# xcodec_CS42526_A.net
KiCad netlist of a schematic drawn in EAGLE
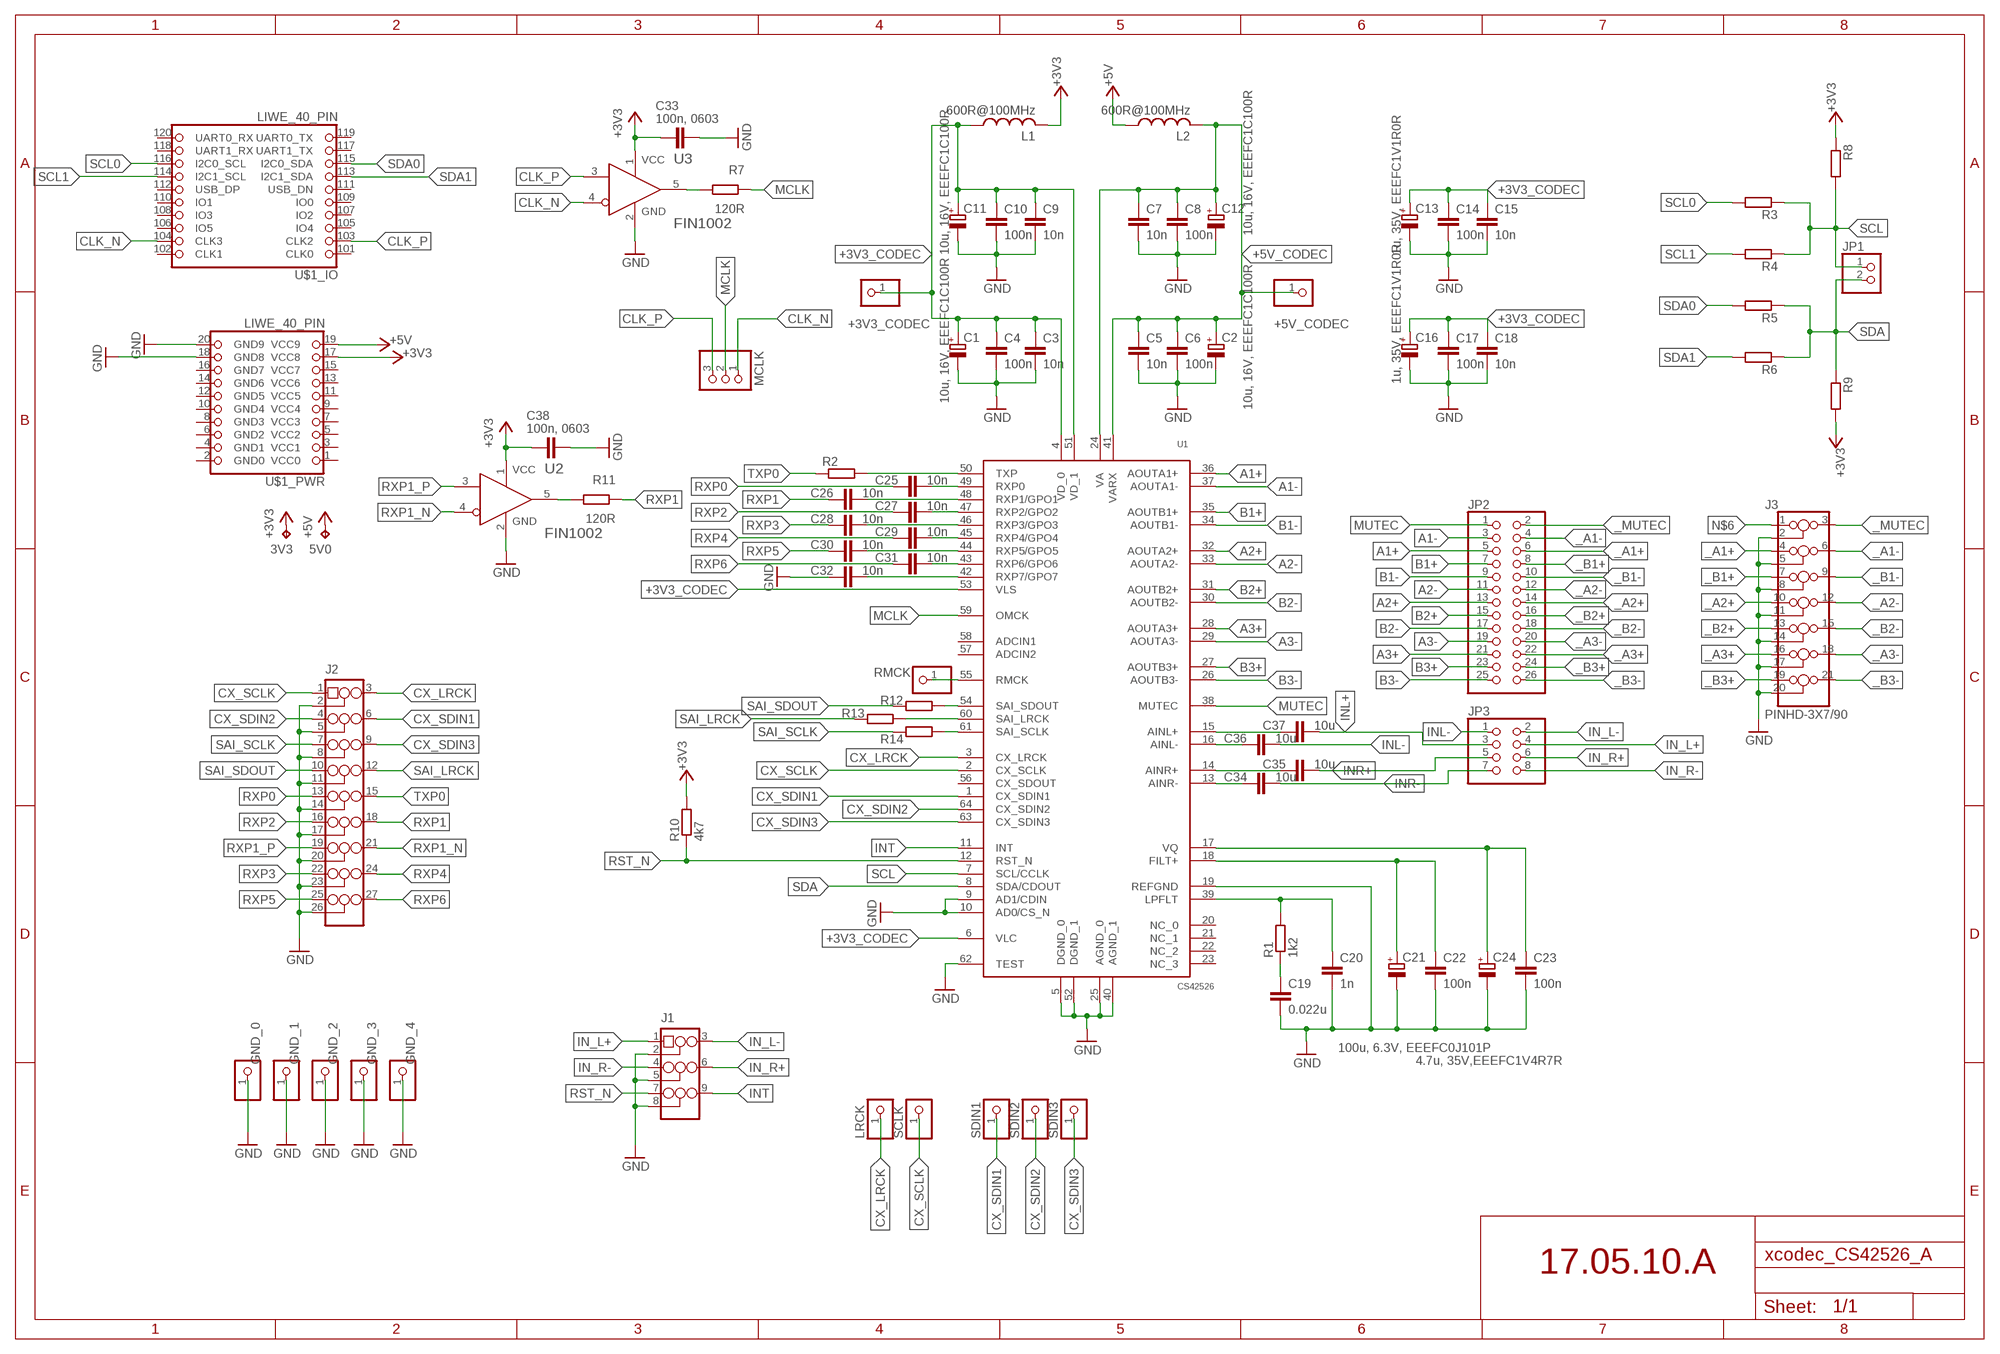
[diagram p0: schematic, sheet 1]

(export (version "E")
  (design (tool "Eeschema 10.0.6"))
  (components
    (comp (ref "+3V3_CODEC")
      (value "PINHD-1X1")
      (footprint "eagle-import:1X01")
      (libsource (lib "eagle-import") (part "PINHD-1X1"))
    )
    (comp (ref "+5V_CODEC")
      (value "PINHD-1X1")
      (footprint "eagle-import:1X01")
      (libsource (lib "eagle-import") (part "PINHD-1X1"))
    )
    (comp (ref "3V3")
      (value "TPTP14R")
      (footprint "eagle-import:TP14R")
      (libsource (lib "eagle-import") (part "TPTP14R"))
    )
    (comp (ref "5V0")
      (value "TPTP14R")
      (footprint "eagle-import:TP14R")
      (libsource (lib "eagle-import") (part "TPTP14R"))
    )
    (comp (ref "C1")
      (value "10u, 16V, EEEFC1C100R")
      (footprint "eagle-import:EEE-FC1V1R0AR")
      (libsource (lib "eagle-import") (part "C-POL_B"))
    )
    (comp (ref "C2")
      (value "10u, 16V, EEEFC1C100R")
      (footprint "eagle-import:EEE-FC1V1R0AR")
      (libsource (lib "eagle-import") (part "C-POL_B"))
    )
    (comp (ref "C3")
      (value "10n")
      (footprint "eagle-import:C0603K")
      (libsource (lib "eagle-import") (part "C-EUC0603K"))
    )
    (comp (ref "C4")
      (value "100n")
      (footprint "eagle-import:C0603K")
      (libsource (lib "eagle-import") (part "C-EUC0603K"))
    )
    (comp (ref "C5")
      (value "10n")
      (footprint "eagle-import:C0603K")
      (libsource (lib "eagle-import") (part "C-EUC0603K"))
    )
    (comp (ref "C6")
      (value "100n")
      (footprint "eagle-import:C0603K")
      (libsource (lib "eagle-import") (part "C-EUC0603K"))
    )
    (comp (ref "C7")
      (value "10n")
      (footprint "eagle-import:C0603K")
      (libsource (lib "eagle-import") (part "C-EUC0603K"))
    )
    (comp (ref "C8")
      (value "100n")
      (footprint "eagle-import:C0603K")
      (libsource (lib "eagle-import") (part "C-EUC0603K"))
    )
    (comp (ref "C9")
      (value "10n")
      (footprint "eagle-import:C0603K")
      (libsource (lib "eagle-import") (part "C-EUC0603K"))
    )
    (comp (ref "C10")
      (value "100n")
      (footprint "eagle-import:C0603K")
      (libsource (lib "eagle-import") (part "C-EUC0603K"))
    )
    (comp (ref "C11")
      (value "10u, 16V, EEEFC1C100R")
      (footprint "eagle-import:EEE-FC1V1R0AR")
      (libsource (lib "eagle-import") (part "C-POL_B"))
    )
    (comp (ref "C12")
      (value "10u, 16V, EEEFC1C100R")
      (footprint "eagle-import:EEE-FC1V1R0AR")
      (libsource (lib "eagle-import") (part "C-POL_B"))
    )
    (comp (ref "C13")
      (value "1u, 35V, EEEFC1V1R0R")
      (footprint "eagle-import:EEE-FC1V1R0AR")
      (libsource (lib "eagle-import") (part "C-POL_B"))
    )
    (comp (ref "C14")
      (value "100n")
      (footprint "eagle-import:C0603K")
      (libsource (lib "eagle-import") (part "C-EUC0603K"))
    )
    (comp (ref "C15")
      (value "10n")
      (footprint "eagle-import:C0603K")
      (libsource (lib "eagle-import") (part "C-EUC0603K"))
    )
    (comp (ref "C16")
      (value "1u, 35V, EEEFC1V1R0R")
      (footprint "eagle-import:EEE-FC1V1R0AR")
      (libsource (lib "eagle-import") (part "C-POL_B"))
    )
    (comp (ref "C17")
      (value "100n")
      (footprint "eagle-import:C0603K")
      (libsource (lib "eagle-import") (part "C-EUC0603K"))
    )
    (comp (ref "C18")
      (value "10n")
      (footprint "eagle-import:C0603K")
      (libsource (lib "eagle-import") (part "C-EUC0603K"))
    )
    (comp (ref "C19")
      (value "0.022u")
      (footprint "eagle-import:C0603K")
      (libsource (lib "eagle-import") (part "C-EUC0603K"))
    )
    (comp (ref "C20")
      (value "1n")
      (footprint "eagle-import:C0603K")
      (libsource (lib "eagle-import") (part "C-EUC0603K"))
    )
    (comp (ref "C21")
      (value "100u, 6.3V, EEEFC0J101P")
      (footprint "eagle-import:EEE-FC1V220P")
      (libsource (lib "eagle-import") (part "C-POL_D"))
    )
    (comp (ref "C22")
      (value "100n")
      (footprint "eagle-import:C0603K")
      (libsource (lib "eagle-import") (part "C-EUC0603K"))
    )
    (comp (ref "C23")
      (value "100n")
      (footprint "eagle-import:C0603K")
      (libsource (lib "eagle-import") (part "C-EUC0603K"))
    )
    (comp (ref "C24")
      (value "4.7u, 35V,EEEFC1V4R7R")
      (footprint "eagle-import:EEE-FC1V1R0AR")
      (libsource (lib "eagle-import") (part "C-POL_B"))
    )
    (comp (ref "C25")
      (value "10n")
      (footprint "eagle-import:C0603K")
      (libsource (lib "eagle-import") (part "C-EUC0603K"))
    )
    (comp (ref "C26")
      (value "10n")
      (footprint "eagle-import:C0603K")
      (libsource (lib "eagle-import") (part "C-EUC0603K"))
    )
    (comp (ref "C27")
      (value "10n")
      (footprint "eagle-import:C0603K")
      (libsource (lib "eagle-import") (part "C-EUC0603K"))
    )
    (comp (ref "C28")
      (value "10n")
      (footprint "eagle-import:C0603K")
      (libsource (lib "eagle-import") (part "C-EUC0603K"))
    )
    (comp (ref "C29")
      (value "10n")
      (footprint "eagle-import:C0603K")
      (libsource (lib "eagle-import") (part "C-EUC0603K"))
    )
    (comp (ref "C30")
      (value "10n")
      (footprint "eagle-import:C0603K")
      (libsource (lib "eagle-import") (part "C-EUC0603K"))
    )
    (comp (ref "C31")
      (value "10n")
      (footprint "eagle-import:C0603K")
      (libsource (lib "eagle-import") (part "C-EUC0603K"))
    )
    (comp (ref "C32")
      (value "10n")
      (footprint "eagle-import:C0603K")
      (libsource (lib "eagle-import") (part "C-EUC0603K"))
    )
    (comp (ref "C33")
      (value "100n, 0603")
      (footprint "eagle-import:C0603K")
      (libsource (lib "eagle-import") (part "C-EUC0603K"))
    )
    (comp (ref "C34")
      (value "10u")
      (footprint "eagle-import:C0603K")
      (libsource (lib "eagle-import") (part "C-EUC0603K"))
    )
    (comp (ref "C35")
      (value "10u")
      (footprint "eagle-import:C0603K")
      (libsource (lib "eagle-import") (part "C-EUC0603K"))
    )
    (comp (ref "C36")
      (value "10u")
      (footprint "eagle-import:C0603K")
      (libsource (lib "eagle-import") (part "C-EUC0603K"))
    )
    (comp (ref "C37")
      (value "10u")
      (footprint "eagle-import:C0603K")
      (libsource (lib "eagle-import") (part "C-EUC0603K"))
    )
    (comp (ref "C38")
      (value "100n, 0603")
      (footprint "eagle-import:C0603K")
      (libsource (lib "eagle-import") (part "C-EUC0603K"))
    )
    (comp (ref "GND_0")
      (value "PINHD-1X1")
      (footprint "eagle-import:1X01")
      (libsource (lib "eagle-import") (part "PINHD-1X1"))
    )
    (comp (ref "GND_1")
      (value "PINHD-1X1")
      (footprint "eagle-import:1X01")
      (libsource (lib "eagle-import") (part "PINHD-1X1"))
    )
    (comp (ref "GND_2")
      (value "PINHD-1X1")
      (footprint "eagle-import:1X01")
      (libsource (lib "eagle-import") (part "PINHD-1X1"))
    )
    (comp (ref "GND_3")
      (value "PINHD-1X1")
      (footprint "eagle-import:1X01")
      (libsource (lib "eagle-import") (part "PINHD-1X1"))
    )
    (comp (ref "GND_4")
      (value "PINHD-1X1")
      (footprint "eagle-import:1X01")
      (libsource (lib "eagle-import") (part "PINHD-1X1"))
    )
    (comp (ref "J1")
      (value "PINHD-3X3/90")
      (footprint "eagle-import:3X03_90")
      (libsource (lib "eagle-import") (part "PINHD-3X3/90"))
    )
    (comp (ref "J2")
      (value "PINHD-3X9/90")
      (footprint "eagle-import:3X9_90")
      (libsource (lib "eagle-import") (part "PINHD-3X9/90"))
    )
    (comp (ref "J3")
      (value "PINHD-3X7/90")
      (footprint "eagle-import:3X07_90")
      (libsource (lib "eagle-import") (part "PINHD-3X7/90"))
    )
    (comp (ref "JP1")
      (value "PINHD-1X2")
      (footprint "eagle-import:1X02")
      (libsource (lib "eagle-import") (part "PINHD-1X2"))
    )
    (comp (ref "JP2")
      (value "PINHD-2X13")
      (footprint "eagle-import:2X13")
      (libsource (lib "eagle-import") (part "PINHD-2X13"))
    )
    (comp (ref "JP3")
      (value "PINHD-2X4")
      (footprint "eagle-import:2X04")
      (libsource (lib "eagle-import") (part "PINHD-2X4"))
    )
    (comp (ref "L1")
      (value "600R@100MHz")
      (footprint "eagle-import:L0603")
      (libsource (lib "eagle-import") (part "L0603(1608)"))
    )
    (comp (ref "L2")
      (value "600R@100MHz")
      (footprint "eagle-import:L0603")
      (libsource (lib "eagle-import") (part "L0603(1608)"))
    )
    (comp (ref "LRCK")
      (value "PINHD-1X1")
      (footprint "eagle-import:1X01")
      (libsource (lib "eagle-import") (part "PINHD-1X1"))
    )
    (comp (ref "MCLK")
      (value "PINHD-1X3")
      (footprint "eagle-import:1X03")
      (libsource (lib "eagle-import") (part "PINHD-1X3"))
    )
    (comp (ref "R1")
      (value "1k2")
      (footprint "eagle-import:R0603")
      (libsource (lib "eagle-import") (part "R-EU_R0603"))
    )
    (comp (ref "R2")
      (value "R-EU_R0603")
      (footprint "eagle-import:R0603")
      (libsource (lib "eagle-import") (part "R-EU_R0603"))
    )
    (comp (ref "R3")
      (value "R-EU_R0603")
      (footprint "eagle-import:R0603")
      (libsource (lib "eagle-import") (part "R-EU_R0603"))
    )
    (comp (ref "R4")
      (value "R-EU_R0603")
      (footprint "eagle-import:R0603")
      (libsource (lib "eagle-import") (part "R-EU_R0603"))
    )
    (comp (ref "R5")
      (value "R-EU_R0603")
      (footprint "eagle-import:R0603")
      (libsource (lib "eagle-import") (part "R-EU_R0603"))
    )
    (comp (ref "R6")
      (value "R-EU_R0603")
      (footprint "eagle-import:R0603")
      (libsource (lib "eagle-import") (part "R-EU_R0603"))
    )
    (comp (ref "R7")
      (value "120R")
      (footprint "eagle-import:R0603")
      (libsource (lib "eagle-import") (part "R-EU_R0603"))
    )
    (comp (ref "R8")
      (value "R-EU_R0603")
      (footprint "eagle-import:R0603")
      (libsource (lib "eagle-import") (part "R-EU_R0603"))
    )
    (comp (ref "R9")
      (value "R-EU_R0603")
      (footprint "eagle-import:R0603")
      (libsource (lib "eagle-import") (part "R-EU_R0603"))
    )
    (comp (ref "R10")
      (value "4k7")
      (footprint "eagle-import:R0603")
      (libsource (lib "eagle-import") (part "R-EU_R0603"))
    )
    (comp (ref "R11")
      (value "120R")
      (footprint "eagle-import:R0603")
      (libsource (lib "eagle-import") (part "R-EU_R0603"))
    )
    (comp (ref "R12")
      (value "R-EU_R0603")
      (footprint "eagle-import:R0603")
      (libsource (lib "eagle-import") (part "R-EU_R0603"))
    )
    (comp (ref "R13")
      (value "R-EU_R0603")
      (footprint "eagle-import:R0603")
      (libsource (lib "eagle-import") (part "R-EU_R0603"))
    )
    (comp (ref "R14")
      (value "R-EU_R0603")
      (footprint "eagle-import:R0603")
      (libsource (lib "eagle-import") (part "R-EU_R0603"))
    )
    (comp (ref "RMCK")
      (value "PINHD-1X1")
      (footprint "eagle-import:1X01")
      (libsource (lib "eagle-import") (part "PINHD-1X1"))
    )
    (comp (ref "SCLK")
      (value "PINHD-1X1")
      (footprint "eagle-import:1X01")
      (libsource (lib "eagle-import") (part "PINHD-1X1"))
    )
    (comp (ref "SDIN1")
      (value "PINHD-1X1")
      (footprint "eagle-import:1X01")
      (libsource (lib "eagle-import") (part "PINHD-1X1"))
    )
    (comp (ref "SDIN2")
      (value "PINHD-1X1")
      (footprint "eagle-import:1X01")
      (libsource (lib "eagle-import") (part "PINHD-1X1"))
    )
    (comp (ref "SDIN3")
      (value "PINHD-1X1")
      (footprint "eagle-import:1X01")
      (libsource (lib "eagle-import") (part "PINHD-1X1"))
    )
    (comp (ref "U$1")
      (value "LIWE_40_PIN")
      (footprint "eagle-import:LIWE_40_PIN_8X8")
      (libsource (lib "eagle-import") (part "LIWE_40_PIN"))
    )
    (comp (ref "U1")
      (value "CS42526")
      (footprint "eagle-import:LQFP_64")
      (libsource (lib "eagle-import") (part "CS42526"))
    )
    (comp (ref "U2")
      (value "FIN1002")
      (footprint "eagle-import:SOT95P280X140-5N")
      (libsource (lib "eagle-import") (part "FIN1002"))
    )
    (comp (ref "U3")
      (value "FIN1002")
      (footprint "eagle-import:SOT95P280X140-5N")
      (libsource (lib "eagle-import") (part "FIN1002"))
    )
  )
  (nets
    (net (code "1") (name "+3V3") (class "Default")
      (node (ref "3V3") (pin "TP") (pinfunction "TP_TP") (pintype "input"))
      (node (ref "C33") (pin "2") (pinfunction "2_2") (pintype "passive"))
      (node (ref "C38") (pin "2") (pinfunction "2_2") (pintype "passive"))
      (node (ref "L1") (pin "2") (pinfunction "2_2") (pintype "passive"))
      (node (ref "R10") (pin "2") (pinfunction "2_2") (pintype "passive"))
      (node (ref "R8") (pin "1") (pinfunction "1_1") (pintype "passive"))
      (node (ref "R9") (pin "2") (pinfunction "2_2") (pintype "passive"))
      (node (ref "U$1") (pin "17") (pinfunction "VCC8_17") (pintype "passive"))
      (node (ref "U2") (pin "1") (pinfunction "VCC_1") (pintype "power_in"))
      (node (ref "U3") (pin "1") (pinfunction "VCC_1") (pintype "power_in"))
    )
    (net (code "2") (name "+3V3_CODEC") (class "Default")
      (node (ref "+3V3_CODEC") (pin "1") (pinfunction "1_1") (pintype "passive"))
      (node (ref "C1") (pin "1") (pinfunction "+_1") (pintype "passive"))
      (node (ref "C10") (pin "1") (pinfunction "1_1") (pintype "passive"))
      (node (ref "C11") (pin "1") (pinfunction "+_1") (pintype "passive"))
      (node (ref "C13") (pin "1") (pinfunction "+_1") (pintype "passive"))
      (node (ref "C14") (pin "1") (pinfunction "1_1") (pintype "passive"))
      (node (ref "C15") (pin "1") (pinfunction "1_1") (pintype "passive"))
      (node (ref "C16") (pin "1") (pinfunction "+_1") (pintype "passive"))
      (node (ref "C17") (pin "1") (pinfunction "1_1") (pintype "passive"))
      (node (ref "C18") (pin "1") (pinfunction "1_1") (pintype "passive"))
      (node (ref "C3") (pin "1") (pinfunction "1_1") (pintype "passive"))
      (node (ref "C4") (pin "1") (pinfunction "1_1") (pintype "passive"))
      (node (ref "C9") (pin "1") (pinfunction "1_1") (pintype "passive"))
      (node (ref "L1") (pin "1") (pinfunction "1_1") (pintype "passive"))
      (node (ref "U1") (pin "4") (pinfunction "VD_0_4") (pintype "bidirectional"))
      (node (ref "U1") (pin "51") (pinfunction "VD_1_51") (pintype "bidirectional"))
      (node (ref "U1") (pin "53") (pinfunction "VLS_53") (pintype "bidirectional"))
      (node (ref "U1") (pin "6") (pinfunction "VLC_6") (pintype "bidirectional"))
    )
    (net (code "3") (name "+5V") (class "Default")
      (node (ref "5V0") (pin "TP") (pinfunction "TP_TP") (pintype "input"))
      (node (ref "L2") (pin "1") (pinfunction "1_1") (pintype "passive"))
      (node (ref "U$1") (pin "19") (pinfunction "VCC9_19") (pintype "passive"))
    )
    (net (code "4") (name "+5V_CODEC") (class "Default")
      (node (ref "+5V_CODEC") (pin "1") (pinfunction "1_1") (pintype "passive"))
      (node (ref "C12") (pin "1") (pinfunction "+_1") (pintype "passive"))
      (node (ref "C2") (pin "1") (pinfunction "+_1") (pintype "passive"))
      (node (ref "C5") (pin "1") (pinfunction "1_1") (pintype "passive"))
      (node (ref "C6") (pin "1") (pinfunction "1_1") (pintype "passive"))
      (node (ref "C7") (pin "1") (pinfunction "1_1") (pintype "passive"))
      (node (ref "C8") (pin "1") (pinfunction "1_1") (pintype "passive"))
      (node (ref "L2") (pin "2") (pinfunction "2_2") (pintype "passive"))
      (node (ref "U1") (pin "24") (pinfunction "VA_24") (pintype "bidirectional"))
      (node (ref "U1") (pin "41") (pinfunction "VARX_41") (pintype "bidirectional"))
    )
    (net (code "5") (name "A1+") (class "Default")
      (node (ref "JP2") (pin "5") (pinfunction "5_5") (pintype "passive"))
      (node (ref "U1") (pin "36") (pinfunction "AOUTA1+_36") (pintype "bidirectional"))
    )
    (net (code "6") (name "A1-") (class "Default")
      (node (ref "JP2") (pin "3") (pinfunction "3_3") (pintype "passive"))
      (node (ref "U1") (pin "37") (pinfunction "AOUTA1-_37") (pintype "bidirectional"))
    )
    (net (code "7") (name "A2+") (class "Default")
      (node (ref "JP2") (pin "13") (pinfunction "13_13") (pintype "passive"))
      (node (ref "U1") (pin "32") (pinfunction "AOUTA2+_32") (pintype "bidirectional"))
    )
    (net (code "8") (name "A2-") (class "Default")
      (node (ref "JP2") (pin "11") (pinfunction "11_11") (pintype "passive"))
      (node (ref "U1") (pin "33") (pinfunction "AOUTA2-_33") (pintype "bidirectional"))
    )
    (net (code "9") (name "A3+") (class "Default")
      (node (ref "JP2") (pin "21") (pinfunction "21_21") (pintype "passive"))
      (node (ref "U1") (pin "28") (pinfunction "AOUTA3+_28") (pintype "bidirectional"))
    )
    (net (code "10") (name "A3-") (class "Default")
      (node (ref "JP2") (pin "19") (pinfunction "19_19") (pintype "passive"))
      (node (ref "U1") (pin "29") (pinfunction "AOUTA3-_29") (pintype "bidirectional"))
    )
    (net (code "11") (name "B1+") (class "Default")
      (node (ref "JP2") (pin "7") (pinfunction "7_7") (pintype "passive"))
      (node (ref "U1") (pin "35") (pinfunction "AOUTB1+_35") (pintype "bidirectional"))
    )
    (net (code "12") (name "B1-") (class "Default")
      (node (ref "JP2") (pin "9") (pinfunction "9_9") (pintype "passive"))
      (node (ref "U1") (pin "34") (pinfunction "AOUTB1-_34") (pintype "bidirectional"))
    )
    (net (code "13") (name "B2+") (class "Default")
      (node (ref "JP2") (pin "15") (pinfunction "15_15") (pintype "passive"))
      (node (ref "U1") (pin "31") (pinfunction "AOUTB2+_31") (pintype "bidirectional"))
    )
    (net (code "14") (name "B2-") (class "Default")
      (node (ref "JP2") (pin "17") (pinfunction "17_17") (pintype "passive"))
      (node (ref "U1") (pin "30") (pinfunction "AOUTB2-_30") (pintype "bidirectional"))
    )
    (net (code "15") (name "B3+") (class "Default")
      (node (ref "JP2") (pin "23") (pinfunction "23_23") (pintype "passive"))
      (node (ref "U1") (pin "27") (pinfunction "AOUTB3+_27") (pintype "bidirectional"))
    )
    (net (code "16") (name "B3-") (class "Default")
      (node (ref "JP2") (pin "25") (pinfunction "25_25") (pintype "passive"))
      (node (ref "U1") (pin "26") (pinfunction "AOUTB3-_26") (pintype "bidirectional"))
    )
    (net (code "17") (name "CLK_N") (class "Default")
      (node (ref "MCLK") (pin "1") (pinfunction "1_1") (pintype "passive"))
      (node (ref "U$1") (pin "104") (pinfunction "CLK3_104") (pintype "passive"))
      (node (ref "U3") (pin "4") (pinfunction "RIN-_4") (pintype "input"))
    )
    (net (code "18") (name "CLK_P") (class "Default")
      (node (ref "MCLK") (pin "3") (pinfunction "3_3") (pintype "passive"))
      (node (ref "U$1") (pin "103") (pinfunction "CLK2_103") (pintype "passive"))
      (node (ref "U3") (pin "3") (pinfunction "RIN+_3") (pintype "input"))
    )
    (net (code "19") (name "CX_LRCK") (class "Default")
      (node (ref "J2") (pin "3") (pinfunction "3_3") (pintype "passive"))
      (node (ref "LRCK") (pin "1") (pinfunction "1_1") (pintype "passive"))
      (node (ref "U1") (pin "3") (pinfunction "CX_LRCK_3") (pintype "bidirectional"))
    )
    (net (code "20") (name "CX_SCLK") (class "Default")
      (node (ref "J2") (pin "1") (pinfunction "1_1") (pintype "passive"))
      (node (ref "SCLK") (pin "1") (pinfunction "1_1") (pintype "passive"))
      (node (ref "U1") (pin "2") (pinfunction "CX_SCLK_2") (pintype "bidirectional"))
    )
    (net (code "21") (name "CX_SDIN1") (class "Default")
      (node (ref "J2") (pin "6") (pinfunction "6_6") (pintype "passive"))
      (node (ref "SDIN1") (pin "1") (pinfunction "1_1") (pintype "passive"))
      (node (ref "U1") (pin "1") (pinfunction "CX_SDIN1_1") (pintype "bidirectional"))
    )
    (net (code "22") (name "CX_SDIN2") (class "Default")
      (node (ref "J2") (pin "4") (pinfunction "4_4") (pintype "passive"))
      (node (ref "SDIN2") (pin "1") (pinfunction "1_1") (pintype "passive"))
      (node (ref "U1") (pin "64") (pinfunction "CX_SDIN2_64") (pintype "bidirectional"))
    )
    (net (code "23") (name "CX_SDIN3") (class "Default")
      (node (ref "J2") (pin "9") (pinfunction "9_9") (pintype "passive"))
      (node (ref "SDIN3") (pin "1") (pinfunction "1_1") (pintype "passive"))
      (node (ref "U1") (pin "63") (pinfunction "CX_SDIN3_63") (pintype "bidirectional"))
    )
    (net (code "24") (name "GND") (class "Default")
      (node (ref "C1") (pin "2") (pinfunction "-_2") (pintype "passive"))
      (node (ref "C10") (pin "2") (pinfunction "2_2") (pintype "passive"))
      (node (ref "C11") (pin "2") (pinfunction "-_2") (pintype "passive"))
      (node (ref "C12") (pin "2") (pinfunction "-_2") (pintype "passive"))
      (node (ref "C13") (pin "2") (pinfunction "-_2") (pintype "passive"))
      (node (ref "C14") (pin "2") (pinfunction "2_2") (pintype "passive"))
      (node (ref "C15") (pin "2") (pinfunction "2_2") (pintype "passive"))
      (node (ref "C16") (pin "2") (pinfunction "-_2") (pintype "passive"))
      (node (ref "C17") (pin "2") (pinfunction "2_2") (pintype "passive"))
      (node (ref "C18") (pin "2") (pinfunction "2_2") (pintype "passive"))
      (node (ref "C19") (pin "2") (pinfunction "2_2") (pintype "passive"))
      (node (ref "C2") (pin "2") (pinfunction "-_2") (pintype "passive"))
      (node (ref "C20") (pin "2") (pinfunction "2_2") (pintype "passive"))
      (node (ref "C21") (pin "2") (pinfunction "-_2") (pintype "passive"))
      (node (ref "C22") (pin "2") (pinfunction "2_2") (pintype "passive"))
      (node (ref "C23") (pin "2") (pinfunction "2_2") (pintype "passive"))
      (node (ref "C24") (pin "2") (pinfunction "-_2") (pintype "passive"))
      (node (ref "C3") (pin "2") (pinfunction "2_2") (pintype "passive"))
      (node (ref "C32") (pin "1") (pinfunction "1_1") (pintype "passive"))
      (node (ref "C33") (pin "1") (pinfunction "1_1") (pintype "passive"))
      (node (ref "C38") (pin "1") (pinfunction "1_1") (pintype "passive"))
      (node (ref "C4") (pin "2") (pinfunction "2_2") (pintype "passive"))
      (node (ref "C5") (pin "2") (pinfunction "2_2") (pintype "passive"))
      (node (ref "C6") (pin "2") (pinfunction "2_2") (pintype "passive"))
      (node (ref "C7") (pin "2") (pinfunction "2_2") (pintype "passive"))
      (node (ref "C8") (pin "2") (pinfunction "2_2") (pintype "passive"))
      (node (ref "C9") (pin "2") (pinfunction "2_2") (pintype "passive"))
      (node (ref "GND_0") (pin "1") (pinfunction "1_1") (pintype "passive"))
      (node (ref "GND_1") (pin "1") (pinfunction "1_1") (pintype "passive"))
      (node (ref "GND_2") (pin "1") (pinfunction "1_1") (pintype "passive"))
      (node (ref "GND_3") (pin "1") (pinfunction "1_1") (pintype "passive"))
      (node (ref "GND_4") (pin "1") (pinfunction "1_1") (pintype "passive"))
      (node (ref "J1") (pin "2") (pinfunction "2_2") (pintype "passive"))
      (node (ref "J1") (pin "5") (pinfunction "5_5") (pintype "passive"))
      (node (ref "J1") (pin "8") (pinfunction "8_8") (pintype "passive"))
      (node (ref "J2") (pin "11") (pinfunction "11_11") (pintype "passive"))
      (node (ref "J2") (pin "14") (pinfunction "14_14") (pintype "passive"))
      (node (ref "J2") (pin "17") (pinfunction "17_17") (pintype "passive"))
      (node (ref "J2") (pin "2") (pinfunction "2_2") (pintype "passive"))
      (node (ref "J2") (pin "20") (pinfunction "20_20") (pintype "passive"))
      (node (ref "J2") (pin "23") (pinfunction "23_23") (pintype "passive"))
      (node (ref "J2") (pin "26") (pinfunction "26_26") (pintype "passive"))
      (node (ref "J2") (pin "5") (pinfunction "5_5") (pintype "passive"))
      (node (ref "J2") (pin "8") (pinfunction "8_8") (pintype "passive"))
      (node (ref "J3") (pin "11") (pinfunction "11_11") (pintype "passive"))
      (node (ref "J3") (pin "14") (pinfunction "14_14") (pintype "passive"))
      (node (ref "J3") (pin "17") (pinfunction "17_17") (pintype "passive"))
      (node (ref "J3") (pin "2") (pinfunction "2_2") (pintype "passive"))
      (node (ref "J3") (pin "20") (pinfunction "20_20") (pintype "passive"))
      (node (ref "J3") (pin "5") (pinfunction "5_5") (pintype "passive"))
      (node (ref "J3") (pin "8") (pinfunction "8_8") (pintype "passive"))
      (node (ref "U$1") (pin "18") (pinfunction "GND8_18") (pintype "passive"))
      (node (ref "U$1") (pin "20") (pinfunction "GND9_20") (pintype "passive"))
      (node (ref "U1") (pin "10") (pinfunction "AD0/CS_N_10") (pintype "bidirectional"))
      (node (ref "U1") (pin "19") (pinfunction "REFGND_19") (pintype "bidirectional"))
      (node (ref "U1") (pin "25") (pinfunction "AGND_0_25") (pintype "bidirectional"))
      (node (ref "U1") (pin "40") (pinfunction "AGND_1_40") (pintype "bidirectional"))
      (node (ref "U1") (pin "5") (pinfunction "DGND_0_5") (pintype "bidirectional"))
      (node (ref "U1") (pin "52") (pinfunction "DGND_1_52") (pintype "bidirectional"))
      (node (ref "U1") (pin "62") (pinfunction "TEST_62") (pintype "bidirectional"))
      (node (ref "U1") (pin "9") (pinfunction "AD1/CDIN_9") (pintype "bidirectional"))
      (node (ref "U2") (pin "2") (pinfunction "GND_2") (pintype "passive"))
      (node (ref "U3") (pin "2") (pinfunction "GND_2") (pintype "passive"))
    )
    (net (code "25") (name "INL+") (class "Default")
      (node (ref "C37") (pin "2") (pinfunction "2_2") (pintype "passive"))
      (node (ref "JP3") (pin "3") (pinfunction "3_3") (pintype "passive"))
    )
    (net (code "26") (name "INL-") (class "Default")
      (node (ref "C36") (pin "2") (pinfunction "2_2") (pintype "passive"))
      (node (ref "JP3") (pin "1") (pinfunction "1_1") (pintype "passive"))
    )
    (net (code "27") (name "INR+") (class "Default")
      (node (ref "C35") (pin "2") (pinfunction "2_2") (pintype "passive"))
      (node (ref "JP3") (pin "5") (pinfunction "5_5") (pintype "passive"))
    )
    (net (code "28") (name "INR-") (class "Default")
      (node (ref "C34") (pin "2") (pinfunction "2_2") (pintype "passive"))
      (node (ref "JP3") (pin "7") (pinfunction "7_7") (pintype "passive"))
    )
    (net (code "29") (name "INT") (class "Default")
      (node (ref "J1") (pin "9") (pinfunction "9_9") (pintype "passive"))
      (node (ref "U1") (pin "11") (pinfunction "INT_11") (pintype "bidirectional"))
    )
    (net (code "30") (name "IN_L+") (class "Default")
      (node (ref "J1") (pin "1") (pinfunction "1_1") (pintype "passive"))
      (node (ref "JP3") (pin "4") (pinfunction "4_4") (pintype "passive"))
    )
    (net (code "31") (name "IN_L-") (class "Default")
      (node (ref "J1") (pin "3") (pinfunction "3_3") (pintype "passive"))
      (node (ref "JP3") (pin "2") (pinfunction "2_2") (pintype "passive"))
    )
    (net (code "32") (name "IN_R+") (class "Default")
      (node (ref "J1") (pin "6") (pinfunction "6_6") (pintype "passive"))
      (node (ref "JP3") (pin "6") (pinfunction "6_6") (pintype "passive"))
    )
    (net (code "33") (name "IN_R-") (class "Default")
      (node (ref "J1") (pin "4") (pinfunction "4_4") (pintype "passive"))
      (node (ref "JP3") (pin "8") (pinfunction "8_8") (pintype "passive"))
    )
    (net (code "34") (name "MCLK") (class "Default")
      (node (ref "MCLK") (pin "2") (pinfunction "2_2") (pintype "passive"))
      (node (ref "R7") (pin "1") (pinfunction "1_1") (pintype "passive"))
      (node (ref "U1") (pin "59") (pinfunction "OMCK_59") (pintype "bidirectional"))
    )
    (net (code "35") (name "MUTEC") (class "Default")
      (node (ref "JP2") (pin "1") (pinfunction "1_1") (pintype "passive"))
      (node (ref "U1") (pin "38") (pinfunction "MUTEC_38") (pintype "bidirectional"))
    )
    (net (code "36") (name "N$6") (class "Default")
      (node (ref "J3") (pin "1") (pinfunction "1_1") (pintype "passive"))
    )
    (net (code "37") (name "Net-(C19-Pad1)") (class "Default")
      (node (ref "C19") (pin "1") (pinfunction "1_1") (pintype "passive"))
      (node (ref "R1") (pin "1") (pinfunction "1_1") (pintype "passive"))
    )
    (net (code "38") (name "Net-(C21-+)") (class "Default")
      (node (ref "C21") (pin "1") (pinfunction "+_1") (pintype "passive"))
      (node (ref "C22") (pin "1") (pinfunction "1_1") (pintype "passive"))
      (node (ref "U1") (pin "18") (pinfunction "FILT+_18") (pintype "bidirectional"))
    )
    (net (code "39") (name "Net-(C24-+)") (class "Default")
      (node (ref "C23") (pin "1") (pinfunction "1_1") (pintype "passive"))
      (node (ref "C24") (pin "1") (pinfunction "+_1") (pintype "passive"))
      (node (ref "U1") (pin "17") (pinfunction "VQ_17") (pintype "bidirectional"))
    )
    (net (code "40") (name "Net-(U1-AINL+)") (class "Default")
      (node (ref "C37") (pin "1") (pinfunction "1_1") (pintype "passive"))
      (node (ref "U1") (pin "15") (pinfunction "AINL+_15") (pintype "bidirectional"))
    )
    (net (code "41") (name "Net-(U1-AINL-)") (class "Default")
      (node (ref "C36") (pin "1") (pinfunction "1_1") (pintype "passive"))
      (node (ref "U1") (pin "16") (pinfunction "AINL-_16") (pintype "bidirectional"))
    )
    (net (code "42") (name "Net-(U1-AINR+)") (class "Default")
      (node (ref "C35") (pin "1") (pinfunction "1_1") (pintype "passive"))
      (node (ref "U1") (pin "14") (pinfunction "AINR+_14") (pintype "bidirectional"))
    )
    (net (code "43") (name "Net-(U1-AINR-)") (class "Default")
      (node (ref "C34") (pin "1") (pinfunction "1_1") (pintype "passive"))
      (node (ref "U1") (pin "13") (pinfunction "AINR-_13") (pintype "bidirectional"))
    )
    (net (code "44") (name "Net-(U1-LPFLT)") (class "Default")
      (node (ref "C20") (pin "1") (pinfunction "1_1") (pintype "passive"))
      (node (ref "R1") (pin "2") (pinfunction "2_2") (pintype "passive"))
      (node (ref "U1") (pin "39") (pinfunction "LPFLT_39") (pintype "bidirectional"))
    )
    (net (code "45") (name "Net-(U1-RMCK)") (class "Default")
      (node (ref "RMCK") (pin "1") (pinfunction "1_1") (pintype "passive"))
      (node (ref "U1") (pin "55") (pinfunction "RMCK_55") (pintype "bidirectional"))
    )
    (net (code "46") (name "Net-(U1-RXP0)") (class "Default")
      (node (ref "C25") (pin "2") (pinfunction "2_2") (pintype "passive"))
      (node (ref "U1") (pin "49") (pinfunction "RXP0_49") (pintype "bidirectional"))
    )
    (net (code "47") (name "Net-(U1-RXP1{slash}GPO1)") (class "Default")
      (node (ref "C26") (pin "2") (pinfunction "2_2") (pintype "passive"))
      (node (ref "U1") (pin "48") (pinfunction "RXP1/GPO1_48") (pintype "bidirectional"))
    )
    (net (code "48") (name "Net-(U1-RXP2{slash}GPO2)") (class "Default")
      (node (ref "C27") (pin "2") (pinfunction "2_2") (pintype "passive"))
      (node (ref "U1") (pin "47") (pinfunction "RXP2/GPO2_47") (pintype "bidirectional"))
    )
    (net (code "49") (name "Net-(U1-RXP3{slash}GPO3)") (class "Default")
      (node (ref "C28") (pin "2") (pinfunction "2_2") (pintype "passive"))
      (node (ref "U1") (pin "46") (pinfunction "RXP3/GPO3_46") (pintype "bidirectional"))
    )
    (net (code "50") (name "Net-(U1-RXP4{slash}GPO4)") (class "Default")
      (node (ref "C29") (pin "2") (pinfunction "2_2") (pintype "passive"))
      (node (ref "U1") (pin "45") (pinfunction "RXP4/GPO4_45") (pintype "bidirectional"))
    )
    (net (code "51") (name "Net-(U1-RXP5{slash}GPO5)") (class "Default")
      (node (ref "C30") (pin "2") (pinfunction "2_2") (pintype "passive"))
      (node (ref "U1") (pin "44") (pinfunction "RXP5/GPO5_44") (pintype "bidirectional"))
    )
    (net (code "52") (name "Net-(U1-RXP6{slash}GPO6)") (class "Default")
      (node (ref "C31") (pin "2") (pinfunction "2_2") (pintype "passive"))
      (node (ref "U1") (pin "43") (pinfunction "RXP6/GPO6_43") (pintype "bidirectional"))
    )
    (net (code "53") (name "Net-(U1-RXP7{slash}GPO7)") (class "Default")
      (node (ref "C32") (pin "2") (pinfunction "2_2") (pintype "passive"))
      (node (ref "U1") (pin "42") (pinfunction "RXP7/GPO7_42") (pintype "bidirectional"))
    )
    (net (code "54") (name "Net-(U1-SAI_LRCK)") (class "Default")
      (node (ref "R13") (pin "1") (pinfunction "1_1") (pintype "passive"))
      (node (ref "U1") (pin "60") (pinfunction "SAI_LRCK_60") (pintype "bidirectional"))
    )
    (net (code "55") (name "Net-(U1-SAI_SCLK)") (class "Default")
      (node (ref "R14") (pin "1") (pinfunction "1_1") (pintype "passive"))
      (node (ref "U1") (pin "61") (pinfunction "SAI_SCLK_61") (pintype "bidirectional"))
    )
    (net (code "56") (name "Net-(U1-SAI_SDOUT)") (class "Default")
      (node (ref "R12") (pin "1") (pinfunction "1_1") (pintype "passive"))
      (node (ref "U1") (pin "54") (pinfunction "SAI_SDOUT_54") (pintype "bidirectional"))
    )
    (net (code "57") (name "Net-(U1-TXP)") (class "Default")
      (node (ref "R2") (pin "2") (pinfunction "2_2") (pintype "passive"))
      (node (ref "U1") (pin "50") (pinfunction "TXP_50") (pintype "bidirectional"))
    )
    (net (code "58") (name "Net-(U2-ROUT)") (class "Default")
      (node (ref "R11") (pin "2") (pinfunction "2_2") (pintype "passive"))
      (node (ref "U2") (pin "5") (pinfunction "ROUT_5") (pintype "output"))
    )
    (net (code "59") (name "Net-(U3-ROUT)") (class "Default")
      (node (ref "R7") (pin "2") (pinfunction "2_2") (pintype "passive"))
      (node (ref "U3") (pin "5") (pinfunction "ROUT_5") (pintype "output"))
    )
    (net (code "60") (name "RST_N") (class "Default")
      (node (ref "J1") (pin "7") (pinfunction "7_7") (pintype "passive"))
      (node (ref "R10") (pin "1") (pinfunction "1_1") (pintype "passive"))
      (node (ref "U1") (pin "12") (pinfunction "RST_N_12") (pintype "bidirectional"))
    )
    (net (code "61") (name "RXP0") (class "Default")
      (node (ref "C25") (pin "1") (pinfunction "1_1") (pintype "passive"))
      (node (ref "J2") (pin "13") (pinfunction "13_13") (pintype "passive"))
    )
    (net (code "62") (name "RXP1") (class "Default")
      (node (ref "C26") (pin "1") (pinfunction "1_1") (pintype "passive"))
      (node (ref "J2") (pin "18") (pinfunction "18_18") (pintype "passive"))
      (node (ref "R11") (pin "1") (pinfunction "1_1") (pintype "passive"))
    )
    (net (code "63") (name "RXP1_N") (class "Default")
      (node (ref "J2") (pin "21") (pinfunction "21_21") (pintype "passive"))
      (node (ref "U2") (pin "4") (pinfunction "RIN-_4") (pintype "input"))
    )
    (net (code "64") (name "RXP1_P") (class "Default")
      (node (ref "J2") (pin "19") (pinfunction "19_19") (pintype "passive"))
      (node (ref "U2") (pin "3") (pinfunction "RIN+_3") (pintype "input"))
    )
    (net (code "65") (name "RXP2") (class "Default")
      (node (ref "C27") (pin "1") (pinfunction "1_1") (pintype "passive"))
      (node (ref "J2") (pin "16") (pinfunction "16_16") (pintype "passive"))
    )
    (net (code "66") (name "RXP3") (class "Default")
      (node (ref "C28") (pin "1") (pinfunction "1_1") (pintype "passive"))
      (node (ref "J2") (pin "22") (pinfunction "22_22") (pintype "passive"))
    )
    (net (code "67") (name "RXP4") (class "Default")
      (node (ref "C29") (pin "1") (pinfunction "1_1") (pintype "passive"))
      (node (ref "J2") (pin "24") (pinfunction "24_24") (pintype "passive"))
    )
    (net (code "68") (name "RXP5") (class "Default")
      (node (ref "C30") (pin "1") (pinfunction "1_1") (pintype "passive"))
      (node (ref "J2") (pin "25") (pinfunction "25_25") (pintype "passive"))
    )
    (net (code "69") (name "RXP6") (class "Default")
      (node (ref "C31") (pin "1") (pinfunction "1_1") (pintype "passive"))
      (node (ref "J2") (pin "27") (pinfunction "27_27") (pintype "passive"))
    )
    (net (code "70") (name "SAI_LRCK") (class "Default")
      (node (ref "J2") (pin "12") (pinfunction "12_12") (pintype "passive"))
      (node (ref "R13") (pin "2") (pinfunction "2_2") (pintype "passive"))
    )
    (net (code "71") (name "SAI_SCLK") (class "Default")
      (node (ref "J2") (pin "7") (pinfunction "7_7") (pintype "passive"))
      (node (ref "R14") (pin "2") (pinfunction "2_2") (pintype "passive"))
    )
    (net (code "72") (name "SAI_SDOUT") (class "Default")
      (node (ref "J2") (pin "10") (pinfunction "10_10") (pintype "passive"))
      (node (ref "R12") (pin "2") (pinfunction "2_2") (pintype "passive"))
    )
    (net (code "73") (name "SCL") (class "Default")
      (node (ref "JP1") (pin "1") (pinfunction "1_1") (pintype "passive"))
      (node (ref "R3") (pin "1") (pinfunction "1_1") (pintype "passive"))
      (node (ref "R4") (pin "1") (pinfunction "1_1") (pintype "passive"))
      (node (ref "R8") (pin "2") (pinfunction "2_2") (pintype "passive"))
      (node (ref "U1") (pin "7") (pinfunction "SCL/CCLK_7") (pintype "bidirectional"))
    )
    (net (code "74") (name "SCL0") (class "Default")
      (node (ref "R3") (pin "2") (pinfunction "2_2") (pintype "passive"))
      (node (ref "U$1") (pin "116") (pinfunction "I2C0_SCL_116") (pintype "passive"))
    )
    (net (code "75") (name "SCL1") (class "Default")
      (node (ref "R4") (pin "2") (pinfunction "2_2") (pintype "passive"))
      (node (ref "U$1") (pin "114") (pinfunction "I2C1_SCL_114") (pintype "passive"))
    )
    (net (code "76") (name "SDA") (class "Default")
      (node (ref "JP1") (pin "2") (pinfunction "2_2") (pintype "passive"))
      (node (ref "R5") (pin "1") (pinfunction "1_1") (pintype "passive"))
      (node (ref "R6") (pin "1") (pinfunction "1_1") (pintype "passive"))
      (node (ref "R9") (pin "1") (pinfunction "1_1") (pintype "passive"))
      (node (ref "U1") (pin "8") (pinfunction "SDA/CDOUT_8") (pintype "bidirectional"))
    )
    (net (code "77") (name "SDA0") (class "Default")
      (node (ref "R5") (pin "2") (pinfunction "2_2") (pintype "passive"))
      (node (ref "U$1") (pin "115") (pinfunction "I2C0_SDA_115") (pintype "passive"))
    )
    (net (code "78") (name "SDA1") (class "Default")
      (node (ref "R6") (pin "2") (pinfunction "2_2") (pintype "passive"))
      (node (ref "U$1") (pin "113") (pinfunction "I2C1_SDA_113") (pintype "passive"))
    )
    (net (code "79") (name "TXP0") (class "Default")
      (node (ref "J2") (pin "15") (pinfunction "15_15") (pintype "passive"))
      (node (ref "R2") (pin "1") (pinfunction "1_1") (pintype "passive"))
    )
    (net (code "80") (name "_A1+") (class "Default")
      (node (ref "J3") (pin "4") (pinfunction "4_4") (pintype "passive"))
      (node (ref "JP2") (pin "6") (pinfunction "6_6") (pintype "passive"))
    )
    (net (code "81") (name "_A1-") (class "Default")
      (node (ref "J3") (pin "6") (pinfunction "6_6") (pintype "passive"))
      (node (ref "JP2") (pin "4") (pinfunction "4_4") (pintype "passive"))
    )
    (net (code "82") (name "_A2+") (class "Default")
      (node (ref "J3") (pin "10") (pinfunction "10_10") (pintype "passive"))
      (node (ref "JP2") (pin "14") (pinfunction "14_14") (pintype "passive"))
    )
    (net (code "83") (name "_A2-") (class "Default")
      (node (ref "J3") (pin "12") (pinfunction "12_12") (pintype "passive"))
      (node (ref "JP2") (pin "12") (pinfunction "12_12") (pintype "passive"))
    )
    (net (code "84") (name "_A3+") (class "Default")
      (node (ref "J3") (pin "16") (pinfunction "16_16") (pintype "passive"))
      (node (ref "JP2") (pin "22") (pinfunction "22_22") (pintype "passive"))
    )
    (net (code "85") (name "_A3-") (class "Default")
      (node (ref "J3") (pin "18") (pinfunction "18_18") (pintype "passive"))
      (node (ref "JP2") (pin "20") (pinfunction "20_20") (pintype "passive"))
    )
    (net (code "86") (name "_B1+") (class "Default")
      (node (ref "J3") (pin "7") (pinfunction "7_7") (pintype "passive"))
      (node (ref "JP2") (pin "8") (pinfunction "8_8") (pintype "passive"))
    )
    (net (code "87") (name "_B1-") (class "Default")
      (node (ref "J3") (pin "9") (pinfunction "9_9") (pintype "passive"))
      (node (ref "JP2") (pin "10") (pinfunction "10_10") (pintype "passive"))
    )
    (net (code "88") (name "_B2+") (class "Default")
      (node (ref "J3") (pin "13") (pinfunction "13_13") (pintype "passive"))
      (node (ref "JP2") (pin "16") (pinfunction "16_16") (pintype "passive"))
    )
    (net (code "89") (name "_B2-") (class "Default")
      (node (ref "J3") (pin "15") (pinfunction "15_15") (pintype "passive"))
      (node (ref "JP2") (pin "18") (pinfunction "18_18") (pintype "passive"))
    )
    (net (code "90") (name "_B3+") (class "Default")
      (node (ref "J3") (pin "19") (pinfunction "19_19") (pintype "passive"))
      (node (ref "JP2") (pin "24") (pinfunction "24_24") (pintype "passive"))
    )
    (net (code "91") (name "_B3-") (class "Default")
      (node (ref "J3") (pin "21") (pinfunction "21_21") (pintype "passive"))
      (node (ref "JP2") (pin "26") (pinfunction "26_26") (pintype "passive"))
    )
    (net (code "92") (name "_MUTEC") (class "Default")
      (node (ref "J3") (pin "3") (pinfunction "3_3") (pintype "passive"))
      (node (ref "JP2") (pin "2") (pinfunction "2_2") (pintype "passive"))
    )
    (net (code "93") (name "unconnected-(U$1A-CLK0-Pad101)") (class "Default")
      (node (ref "U$1") (pin "101") (pinfunction "CLK0_101") (pintype "passive"))
    )
    (net (code "94") (name "unconnected-(U$1A-CLK1-Pad102)") (class "Default")
      (node (ref "U$1") (pin "102") (pinfunction "CLK1_102") (pintype "passive"))
    )
    (net (code "95") (name "unconnected-(U$1A-IO0-Pad109)") (class "Default")
      (node (ref "U$1") (pin "109") (pinfunction "IO0_109") (pintype "passive"))
    )
    (net (code "96") (name "unconnected-(U$1A-IO1-Pad110)") (class "Default")
      (node (ref "U$1") (pin "110") (pinfunction "IO1_110") (pintype "passive"))
    )
    (net (code "97") (name "unconnected-(U$1A-IO2-Pad107)") (class "Default")
      (node (ref "U$1") (pin "107") (pinfunction "IO2_107") (pintype "passive"))
    )
    (net (code "98") (name "unconnected-(U$1A-IO3-Pad108)") (class "Default")
      (node (ref "U$1") (pin "108") (pinfunction "IO3_108") (pintype "passive"))
    )
    (net (code "99") (name "unconnected-(U$1A-IO4-Pad105)") (class "Default")
      (node (ref "U$1") (pin "105") (pinfunction "IO4_105") (pintype "passive"))
    )
    (net (code "100") (name "unconnected-(U$1A-IO5-Pad106)") (class "Default")
      (node (ref "U$1") (pin "106") (pinfunction "IO5_106") (pintype "passive"))
    )
    (net (code "101") (name "unconnected-(U$1A-UART0_RX-Pad120)") (class "Default")
      (node (ref "U$1") (pin "120") (pinfunction "UART0_RX_120") (pintype "passive"))
    )
    (net (code "102") (name "unconnected-(U$1A-UART0_TX-Pad119)") (class "Default")
      (node (ref "U$1") (pin "119") (pinfunction "UART0_TX_119") (pintype "passive"))
    )
    (net (code "103") (name "unconnected-(U$1A-UART1_RX-Pad118)") (class "Default")
      (node (ref "U$1") (pin "118") (pinfunction "UART1_RX_118") (pintype "passive"))
    )
    (net (code "104") (name "unconnected-(U$1A-UART1_TX-Pad117)") (class "Default")
      (node (ref "U$1") (pin "117") (pinfunction "UART1_TX_117") (pintype "passive"))
    )
    (net (code "105") (name "unconnected-(U$1A-USB_DN-Pad111)") (class "Default")
      (node (ref "U$1") (pin "111") (pinfunction "USB_DN_111") (pintype "passive"))
    )
    (net (code "106") (name "unconnected-(U$1A-USB_DP-Pad112)") (class "Default")
      (node (ref "U$1") (pin "112") (pinfunction "USB_DP_112") (pintype "passive"))
    )
    (net (code "107") (name "unconnected-(U$1B-GND0-Pad2)") (class "Default")
      (node (ref "U$1") (pin "2") (pinfunction "GND0_2") (pintype "passive"))
    )
    (net (code "108") (name "unconnected-(U$1B-GND1-Pad4)") (class "Default")
      (node (ref "U$1") (pin "4") (pinfunction "GND1_4") (pintype "passive"))
    )
    (net (code "109") (name "unconnected-(U$1B-GND2-Pad6)") (class "Default")
      (node (ref "U$1") (pin "6") (pinfunction "GND2_6") (pintype "passive"))
    )
    (net (code "110") (name "unconnected-(U$1B-GND3-Pad8)") (class "Default")
      (node (ref "U$1") (pin "8") (pinfunction "GND3_8") (pintype "passive"))
    )
    (net (code "111") (name "unconnected-(U$1B-GND4-Pad10)") (class "Default")
      (node (ref "U$1") (pin "10") (pinfunction "GND4_10") (pintype "passive"))
    )
    (net (code "112") (name "unconnected-(U$1B-GND5-Pad12)") (class "Default")
      (node (ref "U$1") (pin "12") (pinfunction "GND5_12") (pintype "passive"))
    )
    (net (code "113") (name "unconnected-(U$1B-GND6-Pad14)") (class "Default")
      (node (ref "U$1") (pin "14") (pinfunction "GND6_14") (pintype "passive"))
    )
    (net (code "114") (name "unconnected-(U$1B-GND7-Pad16)") (class "Default")
      (node (ref "U$1") (pin "16") (pinfunction "GND7_16") (pintype "passive"))
    )
    (net (code "115") (name "unconnected-(U$1B-VCC0-Pad1)") (class "Default")
      (node (ref "U$1") (pin "1") (pinfunction "VCC0_1") (pintype "passive"))
    )
    (net (code "116") (name "unconnected-(U$1B-VCC1-Pad3)") (class "Default")
      (node (ref "U$1") (pin "3") (pinfunction "VCC1_3") (pintype "passive"))
    )
    (net (code "117") (name "unconnected-(U$1B-VCC2-Pad5)") (class "Default")
      (node (ref "U$1") (pin "5") (pinfunction "VCC2_5") (pintype "passive"))
    )
    (net (code "118") (name "unconnected-(U$1B-VCC3-Pad7)") (class "Default")
      (node (ref "U$1") (pin "7") (pinfunction "VCC3_7") (pintype "passive"))
    )
    (net (code "119") (name "unconnected-(U$1B-VCC4-Pad9)") (class "Default")
      (node (ref "U$1") (pin "9") (pinfunction "VCC4_9") (pintype "passive"))
    )
    (net (code "120") (name "unconnected-(U$1B-VCC5-Pad11)") (class "Default")
      (node (ref "U$1") (pin "11") (pinfunction "VCC5_11") (pintype "passive"))
    )
    (net (code "121") (name "unconnected-(U$1B-VCC6-Pad13)") (class "Default")
      (node (ref "U$1") (pin "13") (pinfunction "VCC6_13") (pintype "passive"))
    )
    (net (code "122") (name "unconnected-(U$1B-VCC7-Pad15)") (class "Default")
      (node (ref "U$1") (pin "15") (pinfunction "VCC7_15") (pintype "passive"))
    )
    (net (code "123") (name "unconnected-(U1-ADCIN1-Pad58)") (class "Default")
      (node (ref "U1") (pin "58") (pinfunction "ADCIN1_58") (pintype "bidirectional"))
    )
    (net (code "124") (name "unconnected-(U1-ADCIN2-Pad57)") (class "Default")
      (node (ref "U1") (pin "57") (pinfunction "ADCIN2_57") (pintype "bidirectional"))
    )
    (net (code "125") (name "unconnected-(U1-CX_SDOUT-Pad56)") (class "Default")
      (node (ref "U1") (pin "56") (pinfunction "CX_SDOUT_56") (pintype "bidirectional"))
    )
    (net (code "126") (name "unconnected-(U1-NC_0-Pad20)") (class "Default")
      (node (ref "U1") (pin "20") (pinfunction "NC_0_20") (pintype "bidirectional"))
    )
    (net (code "127") (name "unconnected-(U1-NC_1-Pad21)") (class "Default")
      (node (ref "U1") (pin "21") (pinfunction "NC_1_21") (pintype "bidirectional"))
    )
    (net (code "128") (name "unconnected-(U1-NC_2-Pad22)") (class "Default")
      (node (ref "U1") (pin "22") (pinfunction "NC_2_22") (pintype "bidirectional"))
    )
    (net (code "129") (name "unconnected-(U1-NC_3-Pad23)") (class "Default")
      (node (ref "U1") (pin "23") (pinfunction "NC_3_23") (pintype "bidirectional"))
    )
  )
)
